# Diagram.net
KiCad netlist of a schematic drawn in EAGLE
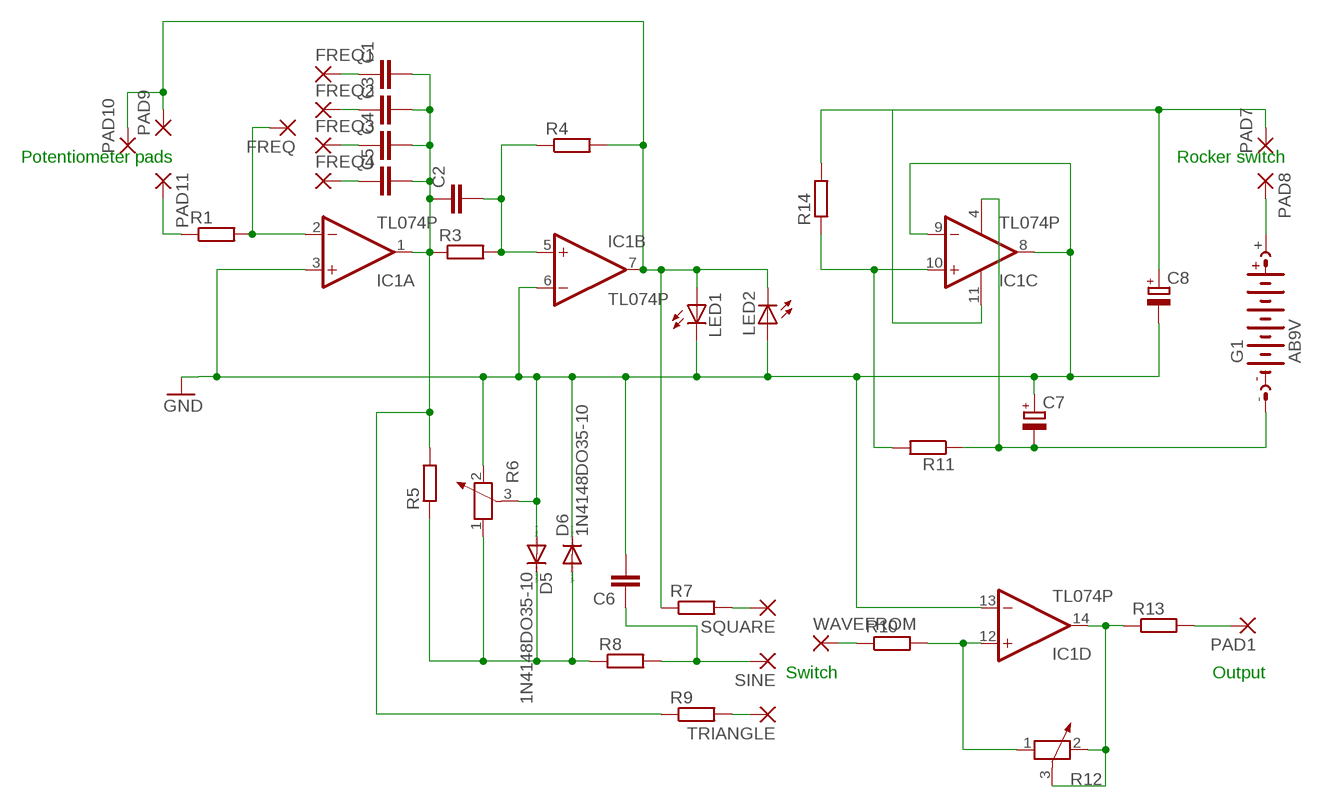
[diagram p0: schematic, sheet 1]

(export (version "E")
  (design (tool "Eeschema 10.0.6"))
  (components
    (comp (ref "C1")
      (value "C-EU050-025X075")
      (footprint "eagle-import:C050-025X075")
      (libsource (lib "eagle-import") (part "C-EU050-025X075"))
    )
    (comp (ref "C2")
      (value "C-EU050-025X075")
      (footprint "eagle-import:C050-025X075")
      (libsource (lib "eagle-import") (part "C-EU050-025X075"))
    )
    (comp (ref "C3")
      (value "C-EU050-025X075")
      (footprint "eagle-import:C050-025X075")
      (libsource (lib "eagle-import") (part "C-EU050-025X075"))
    )
    (comp (ref "C4")
      (value "C-EU050-025X075")
      (footprint "eagle-import:C050-025X075")
      (libsource (lib "eagle-import") (part "C-EU050-025X075"))
    )
    (comp (ref "C5")
      (value "C-EU050-025X075")
      (footprint "eagle-import:C050-025X075")
      (libsource (lib "eagle-import") (part "C-EU050-025X075"))
    )
    (comp (ref "C6")
      (value "C-EU050-025X075")
      (footprint "eagle-import:C050-025X075")
      (libsource (lib "eagle-import") (part "C-EU050-025X075"))
    )
    (comp (ref "C7")
      (value "CPOL-EUE5-5")
      (footprint "eagle-import:E5-5")
      (libsource (lib "eagle-import") (part "CPOL-EUE5-5"))
    )
    (comp (ref "C8")
      (value "CPOL-EUE5-5")
      (footprint "eagle-import:E5-5")
      (libsource (lib "eagle-import") (part "CPOL-EUE5-5"))
    )
    (comp (ref "D5")
      (value "1N4148DO35-10")
      (footprint "eagle-import:DO35-10")
      (libsource (lib "eagle-import") (part "1N4148DO35-10"))
    )
    (comp (ref "D6")
      (value "1N4148DO35-10")
      (footprint "eagle-import:DO35-10")
      (libsource (lib "eagle-import") (part "1N4148DO35-10"))
    )
    (comp (ref "FREQ")
      (value "2,54/1,0")
      (footprint "eagle-import:2,54_1,0")
      (libsource (lib "eagle-import") (part "2,54/1,0"))
    )
    (comp (ref "FREQ1")
      (value "2,54/1,0")
      (footprint "eagle-import:2,54_1,0")
      (libsource (lib "eagle-import") (part "2,54/1,0"))
    )
    (comp (ref "FREQ2")
      (value "2,54/1,0")
      (footprint "eagle-import:2,54_1,0")
      (libsource (lib "eagle-import") (part "2,54/1,0"))
    )
    (comp (ref "FREQ3")
      (value "2,54/1,0")
      (footprint "eagle-import:2,54_1,0")
      (libsource (lib "eagle-import") (part "2,54/1,0"))
    )
    (comp (ref "FREQ4")
      (value "2,54/1,0")
      (footprint "eagle-import:2,54_1,0")
      (libsource (lib "eagle-import") (part "2,54/1,0"))
    )
    (comp (ref "G1")
      (value "AB9V")
      (footprint "eagle-import:AB9V")
      (libsource (lib "eagle-import") (part "AB9V"))
    )
    (comp (ref "IC1")
      (value "TL074P")
      (footprint "eagle-import:DIL14")
      (fields (field (name "SPICEPREFIX") "J"))
      (libsource (lib "eagle-import") (part "TL074P"))
    )
    (comp (ref "LED1")
      (value "LED5MM")
      (footprint "eagle-import:LED5MM")
      (libsource (lib "eagle-import") (part "LED5MM"))
    )
    (comp (ref "LED2")
      (value "LED5MM")
      (footprint "eagle-import:LED5MM")
      (libsource (lib "eagle-import") (part "LED5MM"))
    )
    (comp (ref "PAD1")
      (value "2,54/1,0")
      (footprint "eagle-import:2,54_1,0")
      (libsource (lib "eagle-import") (part "2,54/1,0"))
    )
    (comp (ref "PAD7")
      (value "2,54/1,0")
      (footprint "eagle-import:2,54_1,0")
      (libsource (lib "eagle-import") (part "2,54/1,0"))
    )
    (comp (ref "PAD8")
      (value "2,54/1,0")
      (footprint "eagle-import:2,54_1,0")
      (libsource (lib "eagle-import") (part "2,54/1,0"))
    )
    (comp (ref "PAD9")
      (value "2,54/1,0")
      (footprint "eagle-import:2,54_1,0")
      (libsource (lib "eagle-import") (part "2,54/1,0"))
    )
    (comp (ref "PAD10")
      (value "2,54/1,0")
      (footprint "eagle-import:2,54_1,0")
      (libsource (lib "eagle-import") (part "2,54/1,0"))
    )
    (comp (ref "PAD11")
      (value "2,54/1,0")
      (footprint "eagle-import:2,54_1,0")
      (libsource (lib "eagle-import") (part "2,54/1,0"))
    )
    (comp (ref "R1")
      (value "R-EU_0207/10")
      (footprint "eagle-import:0207_10")
      (libsource (lib "eagle-import") (part "R-EU_0207/10"))
    )
    (comp (ref "R3")
      (value "R-EU_0207/10")
      (footprint "eagle-import:0207_10")
      (libsource (lib "eagle-import") (part "R-EU_0207/10"))
    )
    (comp (ref "R4")
      (value "R-EU_0207/10")
      (footprint "eagle-import:0207_10")
      (libsource (lib "eagle-import") (part "R-EU_0207/10"))
    )
    (comp (ref "R5")
      (value "R-EU_0207/10")
      (footprint "eagle-import:0207_10")
      (libsource (lib "eagle-import") (part "R-EU_0207/10"))
    )
    (comp (ref "R6")
      (value "POTENTIOMETER_PT-10")
      (footprint "eagle-import:PT-10")
      (libsource (lib "eagle-import") (part "POTENTIOMETER_PT-10"))
    )
    (comp (ref "R7")
      (value "R-EU_0207/10")
      (footprint "eagle-import:0207_10")
      (libsource (lib "eagle-import") (part "R-EU_0207/10"))
    )
    (comp (ref "R8")
      (value "R-EU_0207/10")
      (footprint "eagle-import:0207_10")
      (libsource (lib "eagle-import") (part "R-EU_0207/10"))
    )
    (comp (ref "R9")
      (value "R-EU_0207/10")
      (footprint "eagle-import:0207_10")
      (libsource (lib "eagle-import") (part "R-EU_0207/10"))
    )
    (comp (ref "R10")
      (value "R-EU_0207/10")
      (footprint "eagle-import:0207_10")
      (libsource (lib "eagle-import") (part "R-EU_0207/10"))
    )
    (comp (ref "R11")
      (value "R-EU_0207/10")
      (footprint "eagle-import:0207_10")
      (libsource (lib "eagle-import") (part "R-EU_0207/10"))
    )
    (comp (ref "R12")
      (value "POTENTIOMETER_PT-10")
      (footprint "eagle-import:PT-10")
      (libsource (lib "eagle-import") (part "POTENTIOMETER_PT-10"))
    )
    (comp (ref "R13")
      (value "R-EU_0207/10")
      (footprint "eagle-import:0207_10")
      (libsource (lib "eagle-import") (part "R-EU_0207/10"))
    )
    (comp (ref "R14")
      (value "R-EU_0207/10")
      (footprint "eagle-import:0207_10")
      (libsource (lib "eagle-import") (part "R-EU_0207/10"))
    )
    (comp (ref "SINE")
      (value "2,54/1,0")
      (footprint "eagle-import:2,54_1,0")
      (libsource (lib "eagle-import") (part "2,54/1,0"))
    )
    (comp (ref "SQUARE")
      (value "2,54/1,0")
      (footprint "eagle-import:2,54_1,0")
      (libsource (lib "eagle-import") (part "2,54/1,0"))
    )
    (comp (ref "TRIANGLE")
      (value "2,54/1,0")
      (footprint "eagle-import:2,54_1,0")
      (libsource (lib "eagle-import") (part "2,54/1,0"))
    )
    (comp (ref "WAVEFROM")
      (value "2,54/1,0")
      (footprint "eagle-import:2,54_1,0")
      (libsource (lib "eagle-import") (part "2,54/1,0"))
    )
  )
  (nets
    (net (code "1") (name "GND") (class "Default")
      (node (ref "C6") (pin "2") (pinfunction "2_2") (pintype "passive"))
      (node (ref "C7") (pin "+") (pinfunction "+_+") (pintype "passive"))
      (node (ref "C8") (pin "-") (pinfunction "-_-") (pintype "passive"))
      (node (ref "D5") (pin "A") (pinfunction "A_A") (pintype "passive"))
      (node (ref "D6") (pin "C") (pinfunction "C_C") (pintype "passive"))
      (node (ref "IC1") (pin "13") (pinfunction "-IN_13") (pintype "input"))
      (node (ref "IC1") (pin "3") (pinfunction "+IN_3") (pintype "input"))
      (node (ref "IC1") (pin "6") (pinfunction "-IN_6") (pintype "input"))
      (node (ref "IC1") (pin "8") (pinfunction "OUT_8") (pintype "output"))
      (node (ref "IC1") (pin "9") (pinfunction "-IN_9") (pintype "input"))
      (node (ref "LED1") (pin "K") (pinfunction "C_K") (pintype "passive"))
      (node (ref "LED2") (pin "A") (pinfunction "A_A") (pintype "passive"))
      (node (ref "R6") (pin "2") (pinfunction "2_2") (pintype "passive"))
      (node (ref "R6") (pin "3") (pinfunction "3_3") (pintype "passive"))
    )
    (net (code "2") (name "Net-(D5-PadC)") (class "Default")
      (node (ref "D5") (pin "C") (pinfunction "C_C") (pintype "passive"))
      (node (ref "D6") (pin "A") (pinfunction "A_A") (pintype "passive"))
      (node (ref "R5") (pin "1") (pinfunction "1_1") (pintype "passive"))
      (node (ref "R6") (pin "1") (pinfunction "1_1") (pintype "passive"))
      (node (ref "R8") (pin "1") (pinfunction "1_1") (pintype "passive"))
    )
    (net (code "3") (name "Net-(FREQ-P)") (class "Default")
      (node (ref "FREQ") (pin "1") (pinfunction "P_1") (pintype "passive"))
      (node (ref "IC1") (pin "2") (pinfunction "-IN_2") (pintype "input"))
      (node (ref "R1") (pin "2") (pinfunction "2_2") (pintype "passive"))
    )
    (net (code "4") (name "Net-(FREQ1-P)") (class "Default")
      (node (ref "C1") (pin "1") (pinfunction "1_1") (pintype "passive"))
      (node (ref "FREQ1") (pin "1") (pinfunction "P_1") (pintype "passive"))
    )
    (net (code "5") (name "Net-(FREQ2-P)") (class "Default")
      (node (ref "C3") (pin "1") (pinfunction "1_1") (pintype "passive"))
      (node (ref "FREQ2") (pin "1") (pinfunction "P_1") (pintype "passive"))
    )
    (net (code "6") (name "Net-(FREQ3-P)") (class "Default")
      (node (ref "C4") (pin "1") (pinfunction "1_1") (pintype "passive"))
      (node (ref "FREQ3") (pin "1") (pinfunction "P_1") (pintype "passive"))
    )
    (net (code "7") (name "Net-(FREQ4-P)") (class "Default")
      (node (ref "C5") (pin "1") (pinfunction "1_1") (pintype "passive"))
      (node (ref "FREQ4") (pin "1") (pinfunction "P_1") (pintype "passive"))
    )
    (net (code "8") (name "Net-(IC1A-OUT)") (class "Default")
      (node (ref "C1") (pin "2") (pinfunction "2_2") (pintype "passive"))
      (node (ref "C2") (pin "1") (pinfunction "1_1") (pintype "passive"))
      (node (ref "C3") (pin "2") (pinfunction "2_2") (pintype "passive"))
      (node (ref "C4") (pin "2") (pinfunction "2_2") (pintype "passive"))
      (node (ref "C5") (pin "2") (pinfunction "2_2") (pintype "passive"))
      (node (ref "IC1") (pin "1") (pinfunction "OUT_1") (pintype "output"))
      (node (ref "R3") (pin "1") (pinfunction "1_1") (pintype "passive"))
      (node (ref "R5") (pin "2") (pinfunction "2_2") (pintype "passive"))
      (node (ref "R9") (pin "1") (pinfunction "1_1") (pintype "passive"))
    )
    (net (code "9") (name "Net-(IC1B-+IN)") (class "Default")
      (node (ref "C2") (pin "2") (pinfunction "2_2") (pintype "passive"))
      (node (ref "IC1") (pin "5") (pinfunction "+IN_5") (pintype "input"))
      (node (ref "R3") (pin "2") (pinfunction "2_2") (pintype "passive"))
      (node (ref "R4") (pin "1") (pinfunction "1_1") (pintype "passive"))
    )
    (net (code "10") (name "Net-(IC1B-OUT)") (class "Default")
      (node (ref "IC1") (pin "7") (pinfunction "OUT_7") (pintype "output"))
      (node (ref "LED1") (pin "A") (pinfunction "A_A") (pintype "passive"))
      (node (ref "LED2") (pin "K") (pinfunction "C_K") (pintype "passive"))
      (node (ref "PAD10") (pin "1") (pinfunction "P_1") (pintype "passive"))
      (node (ref "PAD9") (pin "1") (pinfunction "P_1") (pintype "passive"))
      (node (ref "R4") (pin "2") (pinfunction "2_2") (pintype "passive"))
      (node (ref "R7") (pin "1") (pinfunction "1_1") (pintype "passive"))
    )
    (net (code "11") (name "Net-(IC1C-+IN)") (class "Default")
      (node (ref "IC1") (pin "10") (pinfunction "+IN_10") (pintype "input"))
      (node (ref "R11") (pin "2") (pinfunction "2_2") (pintype "passive"))
      (node (ref "R14") (pin "1") (pinfunction "1_1") (pintype "passive"))
    )
    (net (code "12") (name "Net-(IC1D-+IN)") (class "Default")
      (node (ref "IC1") (pin "12") (pinfunction "+IN_12") (pintype "input"))
      (node (ref "R10") (pin "2") (pinfunction "2_2") (pintype "passive"))
      (node (ref "R12") (pin "1") (pinfunction "1_1") (pintype "passive"))
    )
    (net (code "13") (name "Net-(IC1D-OUT)") (class "Default")
      (node (ref "IC1") (pin "14") (pinfunction "OUT_14") (pintype "output"))
      (node (ref "R12") (pin "2") (pinfunction "2_2") (pintype "passive"))
      (node (ref "R12") (pin "3") (pinfunction "3_3") (pintype "passive"))
      (node (ref "R13") (pin "1") (pinfunction "1_1") (pintype "passive"))
    )
    (net (code "14") (name "Net-(IC1E-V+)") (class "Default")
      (node (ref "C7") (pin "-") (pinfunction "-_-") (pintype "passive"))
      (node (ref "G1") (pin "-") (pinfunction "-_-") (pintype "passive"))
      (node (ref "IC1") (pin "4") (pinfunction "V+_4") (pintype "power_in"))
      (node (ref "R11") (pin "1") (pinfunction "1_1") (pintype "passive"))
    )
    (net (code "15") (name "Net-(IC1E-V-)") (class "Default")
      (node (ref "C8") (pin "+") (pinfunction "+_+") (pintype "passive"))
      (node (ref "IC1") (pin "11") (pinfunction "V-_11") (pintype "power_in"))
      (node (ref "PAD7") (pin "1") (pinfunction "P_1") (pintype "passive"))
      (node (ref "R14") (pin "2") (pinfunction "2_2") (pintype "passive"))
    )
    (net (code "16") (name "Net-(PAD1-P)") (class "Default")
      (node (ref "PAD1") (pin "1") (pinfunction "P_1") (pintype "passive"))
      (node (ref "R13") (pin "2") (pinfunction "2_2") (pintype "passive"))
    )
    (net (code "17") (name "Net-(PAD8-P)") (class "Default")
      (node (ref "G1") (pin "+") (pinfunction "+_+") (pintype "passive"))
      (node (ref "PAD8") (pin "1") (pinfunction "P_1") (pintype "passive"))
    )
    (net (code "18") (name "Net-(PAD11-P)") (class "Default")
      (node (ref "PAD11") (pin "1") (pinfunction "P_1") (pintype "passive"))
      (node (ref "R1") (pin "1") (pinfunction "1_1") (pintype "passive"))
    )
    (net (code "19") (name "Net-(SINE-P)") (class "Default")
      (node (ref "C6") (pin "1") (pinfunction "1_1") (pintype "passive"))
      (node (ref "R8") (pin "2") (pinfunction "2_2") (pintype "passive"))
      (node (ref "SINE") (pin "1") (pinfunction "P_1") (pintype "passive"))
    )
    (net (code "20") (name "Net-(SQUARE-P)") (class "Default")
      (node (ref "R7") (pin "2") (pinfunction "2_2") (pintype "passive"))
      (node (ref "SQUARE") (pin "1") (pinfunction "P_1") (pintype "passive"))
    )
    (net (code "21") (name "Net-(TRIANGLE-P)") (class "Default")
      (node (ref "R9") (pin "2") (pinfunction "2_2") (pintype "passive"))
      (node (ref "TRIANGLE") (pin "1") (pinfunction "P_1") (pintype "passive"))
    )
    (net (code "22") (name "Net-(WAVEFROM-P)") (class "Default")
      (node (ref "R10") (pin "1") (pinfunction "1_1") (pintype "passive"))
      (node (ref "WAVEFROM") (pin "1") (pinfunction "P_1") (pintype "passive"))
    )
  )
)
